# Coil_Driver_Rev_A-3V_PCH-1.net
KiCad netlist of a schematic drawn in Altium Designer
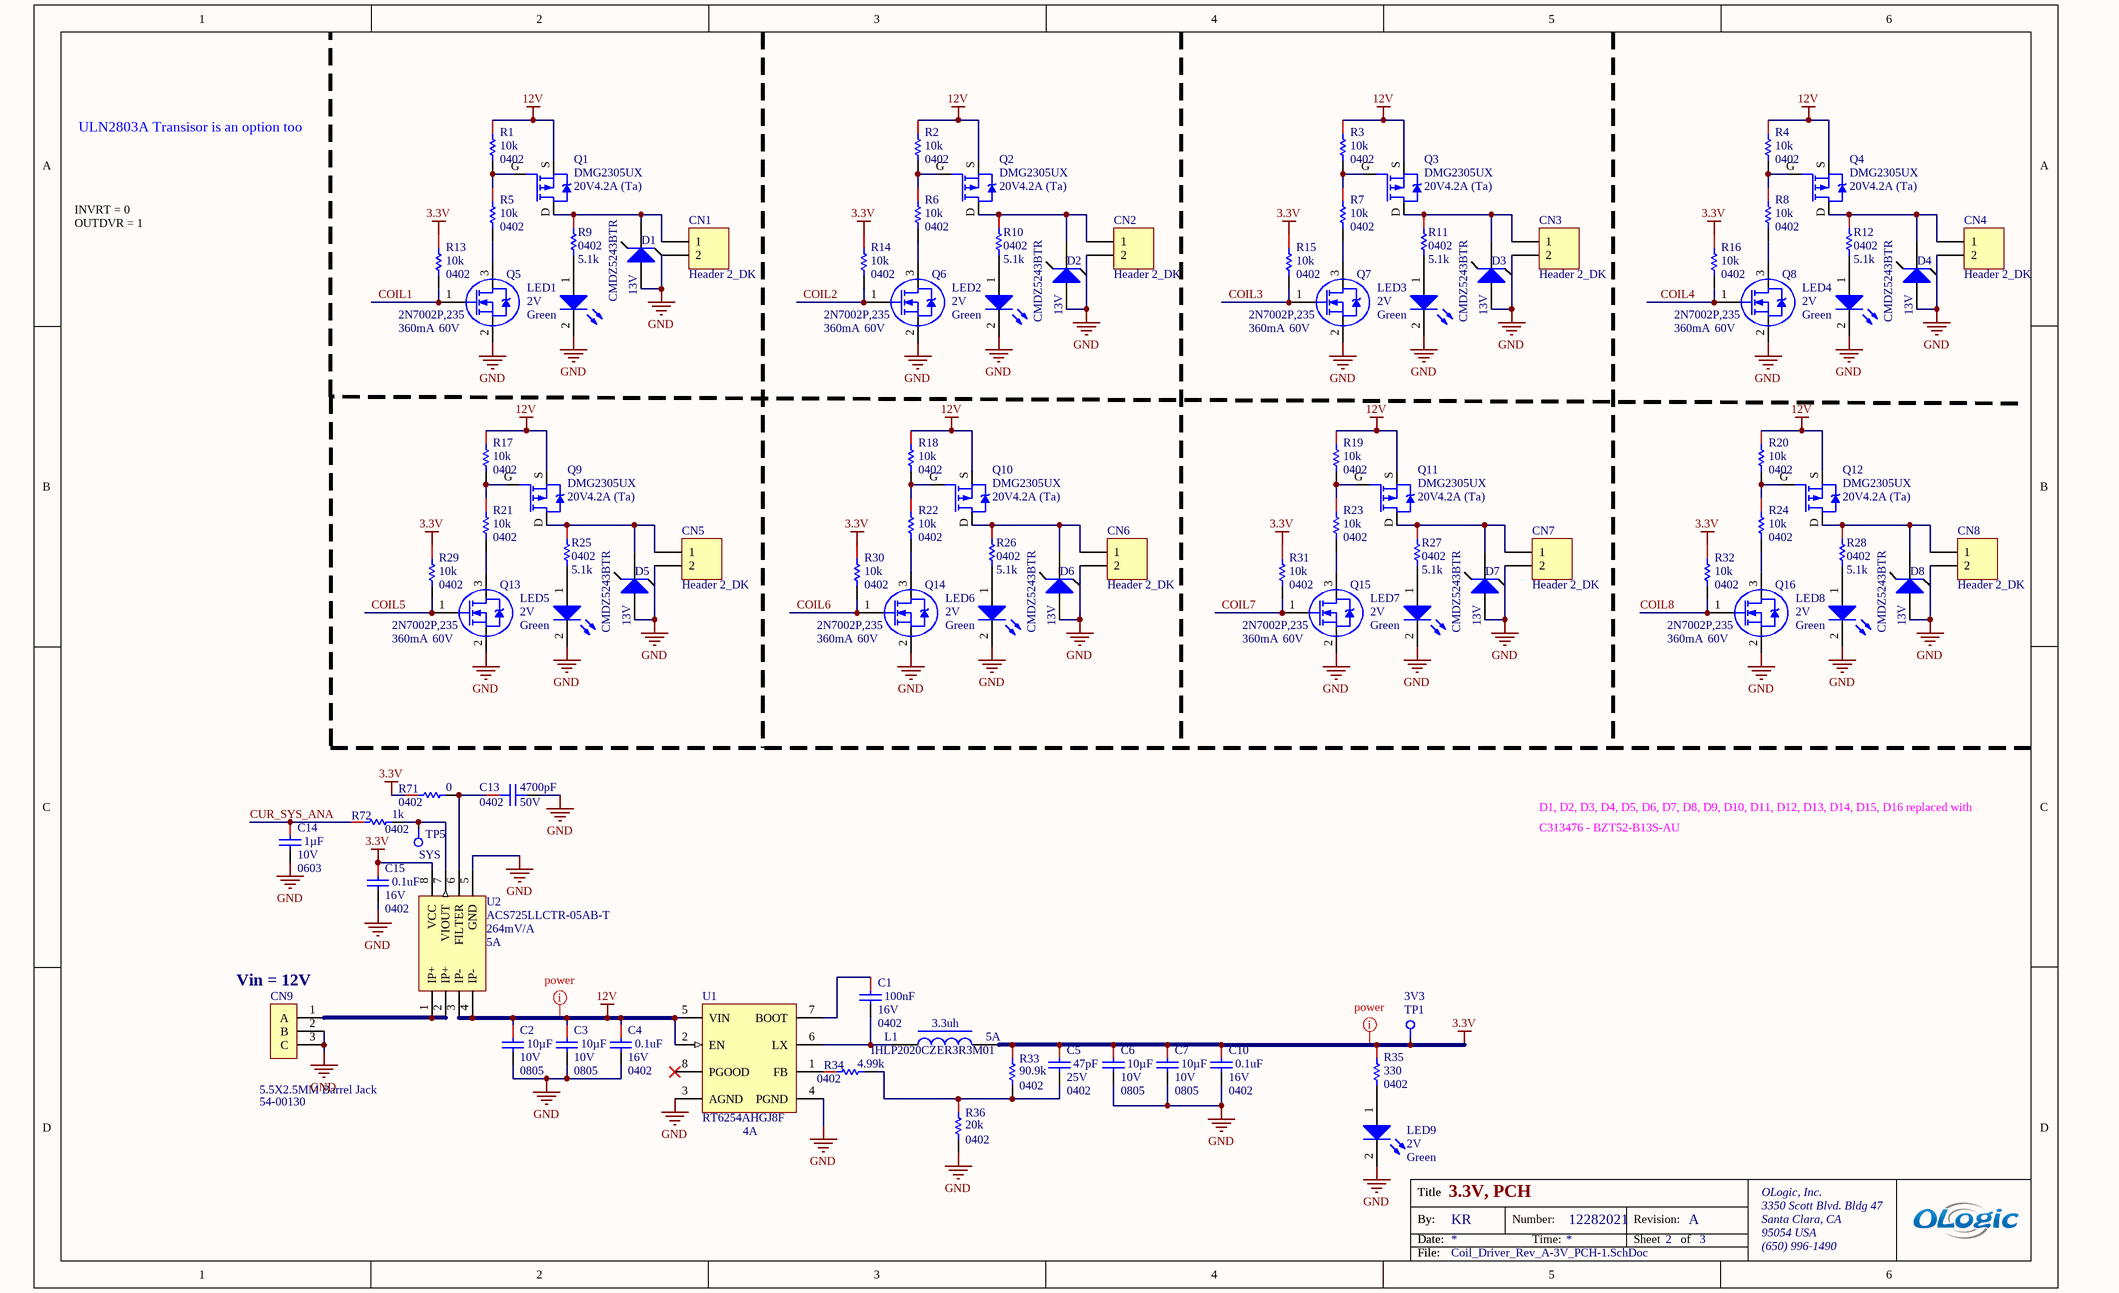
[diagram p0: Coil_Driver_Rev_A-3V_PCH-1.SchDoc]

(export (version "E")
  (design (tool "Eeschema 10.0.6"))
  (components
    (comp (ref "C1")
      (value "CAP CER 0.1UF 16V X5R 0402")
      (footprint "CAPC0402(1005)_L")
      (description "±10% 16V Ceramic Capacitor X5R 0402 (1005 Metric)")
      (fields
        (field (name "VOLTAGE (RATED)") "16V")
        (field (name "PACKAGE (IMPERIAL)") "0402")
        (field (name "TOLERANCE") "10%")
        (field (name "CAPACITANCE") "100nF")
        (field (name "MANUFACTURER") "Taiyo Yuden")
      )
      (libsource (lib "OLogic Nexus Vault") (part "OL_Capacitor"))
    )
    (comp (ref "C2")
      (value "CAP CER 10UF 10V X7R 0805")
      (footprint "CAPC0805(2012)_L")
      (description "10µF ±10% 10V Ceramic Capacitor X7R 0805 (2012 Metric)")
      (fields
        (field (name "VOLTAGE (RATED)") "10V")
        (field (name "PACKAGE (IMPERIAL)") "0805")
        (field (name "CAPACITANCE") "10µF")
        (field (name "TOLERANCE") "10%")
        (field (name "MANUFACTURER PART NUMBER") "GRM21BR71A106KA73K")
      )
      (libsource (lib "OLogic Nexus Vault") (part "OL_Capacitor"))
    )
    (comp (ref "C3")
      (value "CAP CER 10UF 10V X7R 0805")
      (footprint "CAPC0805(2012)_L")
      (description "10µF ±10% 10V Ceramic Capacitor X7R 0805 (2012 Metric)")
      (fields
        (field (name "VOLTAGE (RATED)") "10V")
        (field (name "PACKAGE (IMPERIAL)") "0805")
        (field (name "CAPACITANCE") "10µF")
        (field (name "TOLERANCE") "10%")
        (field (name "MANUFACTURER PART NUMBER") "GRM21BR71A106KA73K")
      )
      (libsource (lib "OLogic Nexus Vault") (part "OL_Capacitor"))
    )
    (comp (ref "C4")
      (value "CAP CER 0.1UF 16V X5R 0402")
      (footprint "CAPC0402(1005)_L")
      (description "±10% 16V Ceramic Capacitor X5R 0402 (1005 Metric)")
      (fields
        (field (name "PACKAGE (IMPERIAL)") "0402")
        (field (name "VOLTAGE (RATED)") "16V")
        (field (name "CAPACITANCE") "0.1uF")
        (field (name "MANUFACTURER") "Taiyo Yuden")
        (field (name "MANUFACTURER PART NUMBER") "EMK105BJ104KV-F")
      )
      (libsource (lib "OLogic Nexus Vault") (part "OL_Capacitor"))
    )
    (comp (ref "C5")
      (value "CAP CER 47PF 25V C0G/NP0 0402")
      (footprint "CAPC0402(1005)_L")
      (description "47pF ±5% 25V Ceramic Capacitor C0G, NP0 0402 (1005 Metric)")
      (fields
        (field (name "PACKAGE (IMPERIAL)") "0402")
        (field (name "VOLTAGE (RATED)") "25V")
        (field (name "CAPACITANCE") "47pF")
        (field (name "MANUFACTURER PART NUMBER") "C0402C470J3GACTU")
        (field (name "TOLERANCE") "5%")
      )
      (libsource (lib "OLogic Nexus Vault") (part "OL_Capacitor"))
    )
    (comp (ref "C6")
      (value "CAP CER 10UF 10V X7R 0805")
      (footprint "CAPC0805(2012)_L")
      (description "10µF ±10% 10V Ceramic Capacitor X7R 0805 (2012 Metric)")
      (fields
        (field (name "VOLTAGE (RATED)") "10V")
        (field (name "PACKAGE (IMPERIAL)") "0805")
        (field (name "CAPACITANCE") "10µF")
        (field (name "TOLERANCE") "10%")
        (field (name "MANUFACTURER PART NUMBER") "GRM21BR71A106KA73K")
      )
      (libsource (lib "OLogic Nexus Vault") (part "OL_Capacitor"))
    )
    (comp (ref "C7")
      (value "CAP CER 10UF 10V X7R 0805")
      (footprint "CAPC0805(2012)_L")
      (description "10µF ±10% 10V Ceramic Capacitor X7R 0805 (2012 Metric)")
      (fields
        (field (name "VOLTAGE (RATED)") "10V")
        (field (name "PACKAGE (IMPERIAL)") "0805")
        (field (name "CAPACITANCE") "10µF")
        (field (name "TOLERANCE") "10%")
        (field (name "MANUFACTURER PART NUMBER") "GRM21BR71A106KA73K")
      )
      (libsource (lib "OLogic Nexus Vault") (part "OL_Capacitor"))
    )
    (comp (ref "C10")
      (value "CAP CER 0.1UF 16V X5R 0402")
      (footprint "CAPC0402(1005)_L")
      (description "±10% 16V Ceramic Capacitor X5R 0402 (1005 Metric)")
      (fields
        (field (name "PACKAGE (IMPERIAL)") "0402")
        (field (name "VOLTAGE (RATED)") "16V")
        (field (name "CAPACITANCE") "0.1uF")
        (field (name "MANUFACTURER") "Taiyo Yuden")
        (field (name "MANUFACTURER PART NUMBER") "EMK105BJ104KV-F")
      )
      (libsource (lib "OLogic Nexus Vault") (part "OL_Capacitor"))
    )
    (comp (ref "C13")
      (value "4700pF")
      (footprint "CAPC0402(1005)_N")
      (description "CAP CER 4700PF 50V X7R 0402")
      (fields
        (field (name "TOLERANCE") "10%")
        (field (name "VOLTAGE (RATED)") "50V")
        (field (name "PACKAGE (IMPERIAL)") "0402")
      )
      (libsource (lib "OLogic Nexus Vault") (part "=Capacitance"))
    )
    (comp (ref "C14")
      (value "1uF")
      (footprint "CAPC0603(1608)_L")
      (description "PREFERRED (<3.3V): CAP CER 1UF 10V X7R 0603")
      (fields
        (field (name "CAPACITANCE") "1µF")
        (field (name "VOLTAGE (RATED)") "10V")
        (field (name "PACKAGE (IMPERIAL)") "0603")
        (field (name "TOLERANCE") "10%")
      )
      (libsource (lib "OLogic Nexus Vault") (part "Bob's Test Generic Capacitor (Non-Polarized)"))
    )
    (comp (ref "C15")
      (value "0.1uF")
      (footprint "CAPC0402(1005)_L")
      (description "CAP CER 0.1UF 16v X7R 0402")
      (fields
        (field (name "VOLTAGE (RATED)") "16V")
        (field (name "PACKAGE (IMPERIAL)") "0402")
        (field (name "TOLERANCE") "10%")
      )
      (libsource (lib "") (part "=Capacitance_1"))
    )
    (comp (ref "CN1")
      (value "Header 2_DK")
      (footprint "HDR1X2")
      (description "Header, 2-Pin")
      (fields
        (field (name "MANUFACTURER PART NUMBER") "826936-2")
        (field (name "MANUFACTURER") "TE Connectivity AMP Connectors")
      )
      (libsource (lib "OLogic Nexus Vault") (part "Header 2_DK"))
    )
    (comp (ref "CN2")
      (value "Header 2_DK")
      (footprint "HDR1X2")
      (description "Header, 2-Pin")
      (fields
        (field (name "MANUFACTURER PART NUMBER") "826936-2")
        (field (name "MANUFACTURER") "TE Connectivity AMP Connectors")
      )
      (libsource (lib "OLogic Nexus Vault") (part "Header 2_DK"))
    )
    (comp (ref "CN3")
      (value "Header 2_DK")
      (footprint "HDR1X2")
      (description "Header, 2-Pin")
      (fields
        (field (name "MANUFACTURER PART NUMBER") "826936-2")
        (field (name "MANUFACTURER") "TE Connectivity AMP Connectors")
      )
      (libsource (lib "OLogic Nexus Vault") (part "Header 2_DK"))
    )
    (comp (ref "CN4")
      (value "Header 2_DK")
      (footprint "HDR1X2")
      (description "Header, 2-Pin")
      (fields
        (field (name "MANUFACTURER PART NUMBER") "826936-2")
        (field (name "MANUFACTURER") "TE Connectivity AMP Connectors")
      )
      (libsource (lib "OLogic Nexus Vault") (part "Header 2_DK"))
    )
    (comp (ref "CN5")
      (value "Header 2_DK")
      (footprint "HDR1X2")
      (description "Header, 2-Pin")
      (fields
        (field (name "MANUFACTURER PART NUMBER") "826936-2")
        (field (name "MANUFACTURER") "TE Connectivity AMP Connectors")
      )
      (libsource (lib "OLogic Nexus Vault") (part "Header 2_DK"))
    )
    (comp (ref "CN6")
      (value "Header 2_DK")
      (footprint "HDR1X2")
      (description "Header, 2-Pin")
      (fields
        (field (name "MANUFACTURER PART NUMBER") "826936-2")
        (field (name "MANUFACTURER") "TE Connectivity AMP Connectors")
      )
      (libsource (lib "OLogic Nexus Vault") (part "Header 2_DK"))
    )
    (comp (ref "CN7")
      (value "Header 2_DK")
      (footprint "HDR1X2")
      (description "Header, 2-Pin")
      (fields
        (field (name "MANUFACTURER PART NUMBER") "826936-2")
        (field (name "MANUFACTURER") "TE Connectivity AMP Connectors")
      )
      (libsource (lib "OLogic Nexus Vault") (part "Header 2_DK"))
    )
    (comp (ref "CN8")
      (value "Header 2_DK")
      (footprint "HDR1X2")
      (description "Header, 2-Pin")
      (fields
        (field (name "MANUFACTURER PART NUMBER") "826936-2")
        (field (name "MANUFACTURER") "TE Connectivity AMP Connectors")
      )
      (libsource (lib "OLogic Nexus Vault") (part "Header 2_DK"))
    )
    (comp (ref "CN9")
      (value "5.5X2.5MM Barrel Jack")
      (footprint "54-00130")
      (description "CONN JACK R/A PCB 5.5X2.5MM")
      (fields
        (field (name "MANUFACTURER PART NUMBER") "54-00130")
        (field (name "MANUFACTURER") "Tensility International Corp")
      )
      (libsource (lib "OLogic Nexus Vault") (part "54-00130"))
    )
    (comp (ref "D1")
      (value "CMDZ5243BTR")
      (footprint "SOD-323")
      (description "DIODE ZENER 13V 250MW SOD323")
      (fields (field (name "TOLERANCE") "5%") (field (name "ZENER VOLTAGE") "13V"))
      (libsource (lib "OLogic Nexus Vault") (part "13V 250mW"))
    )
    (comp (ref "D2")
      (value "CMDZ5243BTR")
      (footprint "SOD-323")
      (description "DIODE ZENER 13V 250MW SOD323")
      (fields (field (name "TOLERANCE") "5%") (field (name "ZENER VOLTAGE") "13V"))
      (libsource (lib "OLogic Nexus Vault") (part "13V 250mW"))
    )
    (comp (ref "D3")
      (value "CMDZ5243BTR")
      (footprint "SOD-323")
      (description "DIODE ZENER 13V 250MW SOD323")
      (fields (field (name "TOLERANCE") "5%") (field (name "ZENER VOLTAGE") "13V"))
      (libsource (lib "OLogic Nexus Vault") (part "13V 250mW"))
    )
    (comp (ref "D4")
      (value "CMDZ5243BTR")
      (footprint "SOD-323")
      (description "DIODE ZENER 13V 250MW SOD323")
      (fields (field (name "TOLERANCE") "5%") (field (name "ZENER VOLTAGE") "13V"))
      (libsource (lib "OLogic Nexus Vault") (part "13V 250mW"))
    )
    (comp (ref "D5")
      (value "CMDZ5243BTR")
      (footprint "SOD-323")
      (description "DIODE ZENER 13V 250MW SOD323")
      (fields (field (name "TOLERANCE") "5%") (field (name "ZENER VOLTAGE") "13V"))
      (libsource (lib "OLogic Nexus Vault") (part "13V 250mW"))
    )
    (comp (ref "D6")
      (value "CMDZ5243BTR")
      (footprint "SOD-323")
      (description "DIODE ZENER 13V 250MW SOD323")
      (fields (field (name "TOLERANCE") "5%") (field (name "ZENER VOLTAGE") "13V"))
      (libsource (lib "OLogic Nexus Vault") (part "13V 250mW"))
    )
    (comp (ref "D7")
      (value "CMDZ5243BTR")
      (footprint "SOD-323")
      (description "DIODE ZENER 13V 250MW SOD323")
      (fields (field (name "TOLERANCE") "5%") (field (name "ZENER VOLTAGE") "13V"))
      (libsource (lib "OLogic Nexus Vault") (part "13V 250mW"))
    )
    (comp (ref "D8")
      (value "CMDZ5243BTR")
      (footprint "SOD-323")
      (description "DIODE ZENER 13V 250MW SOD323")
      (fields (field (name "TOLERANCE") "5%") (field (name "ZENER VOLTAGE") "13V"))
      (libsource (lib "OLogic Nexus Vault") (part "13V 250mW"))
    )
    (comp (ref "L1")
      (value "IHLP2020CZER3R3M01")
      (footprint "INDP5252X30N")
      (description "FIXED IND 3.3UH 5A 54.7 MOHM SMD")
      (fields
        (field (name "TOLERANCE") "20%")
        (field (name "INDUCTANCE") "3.3uh")
        (field (name "CURRENT RATING") "5A")
      )
      (libsource (lib "OLogic Nexus Vault") (part "INDUCTOR SHIELDED 150UH .53A SMD"))
    )
    (comp (ref "LED1")
      (value "LTST-C191KGKT")
      (footprint "SM-LED-0603")
      (description "LED GREEN CLEAR THIN 0603 SMD")
      (fields
        (field (name "MANUFACTURER") "Lite-On Inc")
        (field (name "VOLTAGE - FORWARD (VF) (TYP)") "2V")
        (field (name "COLOR") "Green")
      )
      (libsource (lib "OLogic Nexus Vault") (part "OL_LED"))
    )
    (comp (ref "LED2")
      (value "LTST-C191KGKT")
      (footprint "SM-LED-0603")
      (description "LED GREEN CLEAR THIN 0603 SMD")
      (fields
        (field (name "MANUFACTURER") "Lite-On Inc")
        (field (name "VOLTAGE - FORWARD (VF) (TYP)") "2V")
        (field (name "COLOR") "Green")
      )
      (libsource (lib "OLogic Nexus Vault") (part "OL_LED"))
    )
    (comp (ref "LED3")
      (value "LTST-C191KGKT")
      (footprint "SM-LED-0603")
      (description "LED GREEN CLEAR THIN 0603 SMD")
      (fields
        (field (name "MANUFACTURER") "Lite-On Inc")
        (field (name "VOLTAGE - FORWARD (VF) (TYP)") "2V")
        (field (name "COLOR") "Green")
      )
      (libsource (lib "OLogic Nexus Vault") (part "OL_LED"))
    )
    (comp (ref "LED4")
      (value "LTST-C191KGKT")
      (footprint "SM-LED-0603")
      (description "LED GREEN CLEAR THIN 0603 SMD")
      (fields
        (field (name "MANUFACTURER") "Lite-On Inc")
        (field (name "VOLTAGE - FORWARD (VF) (TYP)") "2V")
        (field (name "COLOR") "Green")
      )
      (libsource (lib "OLogic Nexus Vault") (part "OL_LED"))
    )
    (comp (ref "LED5")
      (value "LTST-C191KGKT")
      (footprint "SM-LED-0603")
      (description "LED GREEN CLEAR THIN 0603 SMD")
      (fields
        (field (name "MANUFACTURER") "Lite-On Inc")
        (field (name "VOLTAGE - FORWARD (VF) (TYP)") "2V")
        (field (name "COLOR") "Green")
      )
      (libsource (lib "OLogic Nexus Vault") (part "OL_LED"))
    )
    (comp (ref "LED6")
      (value "LTST-C191KGKT")
      (footprint "SM-LED-0603")
      (description "LED GREEN CLEAR THIN 0603 SMD")
      (fields
        (field (name "MANUFACTURER") "Lite-On Inc")
        (field (name "VOLTAGE - FORWARD (VF) (TYP)") "2V")
        (field (name "COLOR") "Green")
      )
      (libsource (lib "OLogic Nexus Vault") (part "OL_LED"))
    )
    (comp (ref "LED7")
      (value "LTST-C191KGKT")
      (footprint "SM-LED-0603")
      (description "LED GREEN CLEAR THIN 0603 SMD")
      (fields
        (field (name "MANUFACTURER") "Lite-On Inc")
        (field (name "VOLTAGE - FORWARD (VF) (TYP)") "2V")
        (field (name "COLOR") "Green")
      )
      (libsource (lib "OLogic Nexus Vault") (part "OL_LED"))
    )
    (comp (ref "LED8")
      (value "LTST-C191KGKT")
      (footprint "SM-LED-0603")
      (description "LED GREEN CLEAR THIN 0603 SMD")
      (fields
        (field (name "MANUFACTURER") "Lite-On Inc")
        (field (name "VOLTAGE - FORWARD (VF) (TYP)") "2V")
        (field (name "COLOR") "Green")
      )
      (libsource (lib "OLogic Nexus Vault") (part "OL_LED"))
    )
    (comp (ref "LED9")
      (value "LTST-C191KGKT")
      (footprint "SM-LED-0603")
      (description "LED GREEN CLEAR THIN 0603 SMD")
      (fields
        (field (name "MANUFACTURER") "Lite-On Inc")
        (field (name "VOLTAGE - FORWARD (VF) (TYP)") "2V")
        (field (name "COLOR") "Green")
      )
      (libsource (lib "OLogic Nexus Vault") (part "OL_LED"))
    )
    (comp (ref "Q1")
      (value "DMG2305UX")
      (footprint "DMG2305UX-7")
      (description "MOSFET P-CH 20V 4.2A SOT23")
      (fields
        (field (name "MANUFACTURER PART NUMBER") "DMG2305UX-7")
        (field (name "MANUFACTURER") "Diodes Incorporated")
        (field (name "CURRENT - CONTINUOUS DRAIN (ID) @ 25°C") "4.2A (Ta)")
        (field (name "DRAIN TO SOURCE VOLTAGE (VDSS)") "20V")
        (field (name "CREATOR") "osman")
      )
      (libsource (lib "OLogic Nexus Vault") (part "DMG2305UX"))
    )
    (comp (ref "Q2")
      (value "DMG2305UX")
      (footprint "DMG2305UX-7")
      (description "MOSFET P-CH 20V 4.2A SOT23")
      (fields
        (field (name "MANUFACTURER PART NUMBER") "DMG2305UX-7")
        (field (name "MANUFACTURER") "Diodes Incorporated")
        (field (name "CURRENT - CONTINUOUS DRAIN (ID) @ 25°C") "4.2A (Ta)")
        (field (name "DRAIN TO SOURCE VOLTAGE (VDSS)") "20V")
        (field (name "CREATOR") "osman")
      )
      (libsource (lib "OLogic Nexus Vault") (part "DMG2305UX"))
    )
    (comp (ref "Q3")
      (value "DMG2305UX")
      (footprint "DMG2305UX-7")
      (description "MOSFET P-CH 20V 4.2A SOT23")
      (fields
        (field (name "MANUFACTURER PART NUMBER") "DMG2305UX-7")
        (field (name "MANUFACTURER") "Diodes Incorporated")
        (field (name "CURRENT - CONTINUOUS DRAIN (ID) @ 25°C") "4.2A (Ta)")
        (field (name "DRAIN TO SOURCE VOLTAGE (VDSS)") "20V")
        (field (name "CREATOR") "osman")
      )
      (libsource (lib "OLogic Nexus Vault") (part "DMG2305UX"))
    )
    (comp (ref "Q4")
      (value "DMG2305UX")
      (footprint "DMG2305UX-7")
      (description "MOSFET P-CH 20V 4.2A SOT23")
      (fields
        (field (name "MANUFACTURER PART NUMBER") "DMG2305UX-7")
        (field (name "MANUFACTURER") "Diodes Incorporated")
        (field (name "CURRENT - CONTINUOUS DRAIN (ID) @ 25°C") "4.2A (Ta)")
        (field (name "DRAIN TO SOURCE VOLTAGE (VDSS)") "20V")
        (field (name "CREATOR") "osman")
      )
      (libsource (lib "OLogic Nexus Vault") (part "DMG2305UX"))
    )
    (comp (ref "Q5")
      (value "2N7002P,235")
      (footprint "SOT23-3L")
      (description "MOSFET N-CH 60V 0.36A SOT-23")
      (fields
        (field (name "CONTINUOUS DRAIN CURRENT (ID)") "360mA")
        (field (name "MANUFACTURER") "NXP Semiconductors")
        (field (name "DRAIN TO SOURCE VOLTAGE (VDSS)") "60V")
      )
      (libsource (lib "OLogic Nexus Vault") (part "2N7002P,235"))
    )
    (comp (ref "Q6")
      (value "2N7002P,235")
      (footprint "SOT23-3L")
      (description "MOSFET N-CH 60V 0.36A SOT-23")
      (fields
        (field (name "CONTINUOUS DRAIN CURRENT (ID)") "360mA")
        (field (name "MANUFACTURER") "NXP Semiconductors")
        (field (name "DRAIN TO SOURCE VOLTAGE (VDSS)") "60V")
      )
      (libsource (lib "OLogic Nexus Vault") (part "2N7002P,235"))
    )
    (comp (ref "Q7")
      (value "2N7002P,235")
      (footprint "SOT23-3L")
      (description "MOSFET N-CH 60V 0.36A SOT-23")
      (fields
        (field (name "CONTINUOUS DRAIN CURRENT (ID)") "360mA")
        (field (name "MANUFACTURER") "NXP Semiconductors")
        (field (name "DRAIN TO SOURCE VOLTAGE (VDSS)") "60V")
      )
      (libsource (lib "OLogic Nexus Vault") (part "2N7002P,235"))
    )
    (comp (ref "Q8")
      (value "2N7002P,235")
      (footprint "SOT23-3L")
      (description "MOSFET N-CH 60V 0.36A SOT-23")
      (fields
        (field (name "CONTINUOUS DRAIN CURRENT (ID)") "360mA")
        (field (name "MANUFACTURER") "NXP Semiconductors")
        (field (name "DRAIN TO SOURCE VOLTAGE (VDSS)") "60V")
      )
      (libsource (lib "OLogic Nexus Vault") (part "2N7002P,235"))
    )
    (comp (ref "Q9")
      (value "DMG2305UX")
      (footprint "DMG2305UX-7")
      (description "MOSFET P-CH 20V 4.2A SOT23")
      (fields
        (field (name "MANUFACTURER PART NUMBER") "DMG2305UX-7")
        (field (name "MANUFACTURER") "Diodes Incorporated")
        (field (name "CURRENT - CONTINUOUS DRAIN (ID) @ 25°C") "4.2A (Ta)")
        (field (name "DRAIN TO SOURCE VOLTAGE (VDSS)") "20V")
        (field (name "CREATOR") "osman")
      )
      (libsource (lib "OLogic Nexus Vault") (part "DMG2305UX"))
    )
    (comp (ref "Q10")
      (value "DMG2305UX")
      (footprint "DMG2305UX-7")
      (description "MOSFET P-CH 20V 4.2A SOT23")
      (fields
        (field (name "MANUFACTURER PART NUMBER") "DMG2305UX-7")
        (field (name "MANUFACTURER") "Diodes Incorporated")
        (field (name "CURRENT - CONTINUOUS DRAIN (ID) @ 25°C") "4.2A (Ta)")
        (field (name "DRAIN TO SOURCE VOLTAGE (VDSS)") "20V")
        (field (name "CREATOR") "osman")
      )
      (libsource (lib "OLogic Nexus Vault") (part "DMG2305UX"))
    )
    (comp (ref "Q11")
      (value "DMG2305UX")
      (footprint "DMG2305UX-7")
      (description "MOSFET P-CH 20V 4.2A SOT23")
      (fields
        (field (name "MANUFACTURER PART NUMBER") "DMG2305UX-7")
        (field (name "MANUFACTURER") "Diodes Incorporated")
        (field (name "CURRENT - CONTINUOUS DRAIN (ID) @ 25°C") "4.2A (Ta)")
        (field (name "DRAIN TO SOURCE VOLTAGE (VDSS)") "20V")
        (field (name "CREATOR") "osman")
      )
      (libsource (lib "OLogic Nexus Vault") (part "DMG2305UX"))
    )
    (comp (ref "Q12")
      (value "DMG2305UX")
      (footprint "DMG2305UX-7")
      (description "MOSFET P-CH 20V 4.2A SOT23")
      (fields
        (field (name "MANUFACTURER PART NUMBER") "DMG2305UX-7")
        (field (name "MANUFACTURER") "Diodes Incorporated")
        (field (name "CURRENT - CONTINUOUS DRAIN (ID) @ 25°C") "4.2A (Ta)")
        (field (name "DRAIN TO SOURCE VOLTAGE (VDSS)") "20V")
        (field (name "CREATOR") "osman")
      )
      (libsource (lib "OLogic Nexus Vault") (part "DMG2305UX"))
    )
    (comp (ref "Q13")
      (value "2N7002P,235")
      (footprint "SOT23-3L")
      (description "MOSFET N-CH 60V 0.36A SOT-23")
      (fields
        (field (name "CONTINUOUS DRAIN CURRENT (ID)") "360mA")
        (field (name "MANUFACTURER") "NXP Semiconductors")
        (field (name "DRAIN TO SOURCE VOLTAGE (VDSS)") "60V")
      )
      (libsource (lib "OLogic Nexus Vault") (part "2N7002P,235"))
    )
    (comp (ref "Q14")
      (value "2N7002P,235")
      (footprint "SOT23-3L")
      (description "MOSFET N-CH 60V 0.36A SOT-23")
      (fields
        (field (name "CONTINUOUS DRAIN CURRENT (ID)") "360mA")
        (field (name "MANUFACTURER") "NXP Semiconductors")
        (field (name "DRAIN TO SOURCE VOLTAGE (VDSS)") "60V")
      )
      (libsource (lib "OLogic Nexus Vault") (part "2N7002P,235"))
    )
    (comp (ref "Q15")
      (value "2N7002P,235")
      (footprint "SOT23-3L")
      (description "MOSFET N-CH 60V 0.36A SOT-23")
      (fields
        (field (name "CONTINUOUS DRAIN CURRENT (ID)") "360mA")
        (field (name "MANUFACTURER") "NXP Semiconductors")
        (field (name "DRAIN TO SOURCE VOLTAGE (VDSS)") "60V")
      )
      (libsource (lib "OLogic Nexus Vault") (part "2N7002P,235"))
    )
    (comp (ref "Q16")
      (value "2N7002P,235")
      (footprint "SOT23-3L")
      (description "MOSFET N-CH 60V 0.36A SOT-23")
      (fields
        (field (name "CONTINUOUS DRAIN CURRENT (ID)") "360mA")
        (field (name "MANUFACTURER") "NXP Semiconductors")
        (field (name "DRAIN TO SOURCE VOLTAGE (VDSS)") "60V")
      )
      (libsource (lib "OLogic Nexus Vault") (part "2N7002P,235"))
    )
    (comp (ref "R1")
      (value "RES 10K OHM 0.1% 1/16W 0402")
      (footprint "RESC0402(1005)_L")
      (description "10 kOhms ±0.1% 0.063W, 1/16W Chip Resistor 0402 (1005 Metric) Automotive AEC-Q200 Thin Film")
      (fields
        (field (name "TOLERANCE") "0.1%")
        (field (name "RESISTANCE") "10k")
        (field (name "CASE CODE (IMPERIAL)") "0402")
      )
      (libsource (lib "OLogic Nexus Vault") (part "OL_Resistor"))
    )
    (comp (ref "R2")
      (value "RES 10K OHM 0.1% 1/16W 0402")
      (footprint "RESC0402(1005)_L")
      (description "10 kOhms ±0.1% 0.063W, 1/16W Chip Resistor 0402 (1005 Metric) Automotive AEC-Q200 Thin Film")
      (fields
        (field (name "TOLERANCE") "0.1%")
        (field (name "RESISTANCE") "10k")
        (field (name "CASE CODE (IMPERIAL)") "0402")
      )
      (libsource (lib "OLogic Nexus Vault") (part "OL_Resistor"))
    )
    (comp (ref "R3")
      (value "RES 10K OHM 0.1% 1/16W 0402")
      (footprint "RESC0402(1005)_L")
      (description "10 kOhms ±0.1% 0.063W, 1/16W Chip Resistor 0402 (1005 Metric) Automotive AEC-Q200 Thin Film")
      (fields
        (field (name "TOLERANCE") "0.1%")
        (field (name "RESISTANCE") "10k")
        (field (name "CASE CODE (IMPERIAL)") "0402")
      )
      (libsource (lib "OLogic Nexus Vault") (part "OL_Resistor"))
    )
    (comp (ref "R4")
      (value "RES 10K OHM 0.1% 1/16W 0402")
      (footprint "RESC0402(1005)_L")
      (description "10 kOhms ±0.1% 0.063W, 1/16W Chip Resistor 0402 (1005 Metric) Automotive AEC-Q200 Thin Film")
      (fields
        (field (name "TOLERANCE") "0.1%")
        (field (name "RESISTANCE") "10k")
        (field (name "CASE CODE (IMPERIAL)") "0402")
      )
      (libsource (lib "OLogic Nexus Vault") (part "OL_Resistor"))
    )
    (comp (ref "R5")
      (value "RES 10K OHM 0.1% 1/16W 0402")
      (footprint "RESC0402(1005)_L")
      (description "10 kOhms ±0.1% 0.063W, 1/16W Chip Resistor 0402 (1005 Metric) Automotive AEC-Q200 Thin Film")
      (fields
        (field (name "TOLERANCE") "0.1%")
        (field (name "RESISTANCE") "10k")
        (field (name "CASE CODE (IMPERIAL)") "0402")
      )
      (libsource (lib "OLogic Nexus Vault") (part "OL_Resistor"))
    )
    (comp (ref "R6")
      (value "RES 10K OHM 0.1% 1/16W 0402")
      (footprint "RESC0402(1005)_L")
      (description "10 kOhms ±0.1% 0.063W, 1/16W Chip Resistor 0402 (1005 Metric) Automotive AEC-Q200 Thin Film")
      (fields
        (field (name "TOLERANCE") "0.1%")
        (field (name "RESISTANCE") "10k")
        (field (name "CASE CODE (IMPERIAL)") "0402")
      )
      (libsource (lib "OLogic Nexus Vault") (part "OL_Resistor"))
    )
    (comp (ref "R7")
      (value "RES 10K OHM 0.1% 1/16W 0402")
      (footprint "RESC0402(1005)_L")
      (description "10 kOhms ±0.1% 0.063W, 1/16W Chip Resistor 0402 (1005 Metric) Automotive AEC-Q200 Thin Film")
      (fields
        (field (name "TOLERANCE") "0.1%")
        (field (name "RESISTANCE") "10k")
        (field (name "CASE CODE (IMPERIAL)") "0402")
      )
      (libsource (lib "OLogic Nexus Vault") (part "OL_Resistor"))
    )
    (comp (ref "R8")
      (value "RES 10K OHM 0.1% 1/16W 0402")
      (footprint "RESC0402(1005)_L")
      (description "10 kOhms ±0.1% 0.063W, 1/16W Chip Resistor 0402 (1005 Metric) Automotive AEC-Q200 Thin Film")
      (fields
        (field (name "TOLERANCE") "0.1%")
        (field (name "RESISTANCE") "10k")
        (field (name "CASE CODE (IMPERIAL)") "0402")
      )
      (libsource (lib "OLogic Nexus Vault") (part "OL_Resistor"))
    )
    (comp (ref "R9")
      (value "5.1K")
      (footprint "RESC0402(1005)_L")
      (description "RES SMD 5.1K OHM 1% 1/10W 0402")
      (fields
        (field (name "PACKAGE (IMPERIAL)") "0402")
        (field (name "RESISTANCE") "5.1k")
        (field (name "POWER") "63mW")
        (field (name "TOLERANCE") "1%")
      )
      (libsource (lib "OLogic Nexus Vault") (part "=Resistance"))
    )
    (comp (ref "R10")
      (value "5.1K")
      (footprint "RESC0402(1005)_L")
      (description "RES SMD 5.1K OHM 1% 1/10W 0402")
      (fields
        (field (name "PACKAGE (IMPERIAL)") "0402")
        (field (name "RESISTANCE") "5.1k")
        (field (name "POWER") "63mW")
        (field (name "TOLERANCE") "1%")
      )
      (libsource (lib "OLogic Nexus Vault") (part "=Resistance"))
    )
    (comp (ref "R11")
      (value "5.1K")
      (footprint "RESC0402(1005)_L")
      (description "RES SMD 5.1K OHM 1% 1/10W 0402")
      (fields
        (field (name "PACKAGE (IMPERIAL)") "0402")
        (field (name "RESISTANCE") "5.1k")
        (field (name "POWER") "63mW")
        (field (name "TOLERANCE") "1%")
      )
      (libsource (lib "OLogic Nexus Vault") (part "=Resistance"))
    )
    (comp (ref "R12")
      (value "5.1K")
      (footprint "RESC0402(1005)_L")
      (description "RES SMD 5.1K OHM 1% 1/10W 0402")
      (fields
        (field (name "PACKAGE (IMPERIAL)") "0402")
        (field (name "RESISTANCE") "5.1k")
        (field (name "POWER") "63mW")
        (field (name "TOLERANCE") "1%")
      )
      (libsource (lib "OLogic Nexus Vault") (part "=Resistance"))
    )
    (comp (ref "R13")
      (value "RES 10K OHM 0.1% 1/16W 0402")
      (footprint "RESC0402(1005)_L")
      (description "10 kOhms ±0.1% 0.063W, 1/16W Chip Resistor 0402 (1005 Metric) Automotive AEC-Q200 Thin Film")
      (fields
        (field (name "TOLERANCE") "0.1%")
        (field (name "RESISTANCE") "10k")
        (field (name "CASE CODE (IMPERIAL)") "0402")
      )
      (libsource (lib "OLogic Nexus Vault") (part "OL_Resistor"))
    )
    (comp (ref "R14")
      (value "RES 10K OHM 0.1% 1/16W 0402")
      (footprint "RESC0402(1005)_L")
      (description "10 kOhms ±0.1% 0.063W, 1/16W Chip Resistor 0402 (1005 Metric) Automotive AEC-Q200 Thin Film")
      (fields
        (field (name "TOLERANCE") "0.1%")
        (field (name "RESISTANCE") "10k")
        (field (name "CASE CODE (IMPERIAL)") "0402")
      )
      (libsource (lib "OLogic Nexus Vault") (part "OL_Resistor"))
    )
    (comp (ref "R15")
      (value "RES 10K OHM 0.1% 1/16W 0402")
      (footprint "RESC0402(1005)_L")
      (description "10 kOhms ±0.1% 0.063W, 1/16W Chip Resistor 0402 (1005 Metric) Automotive AEC-Q200 Thin Film")
      (fields
        (field (name "TOLERANCE") "0.1%")
        (field (name "RESISTANCE") "10k")
        (field (name "CASE CODE (IMPERIAL)") "0402")
      )
      (libsource (lib "OLogic Nexus Vault") (part "OL_Resistor"))
    )
    (comp (ref "R16")
      (value "RES 10K OHM 0.1% 1/16W 0402")
      (footprint "RESC0402(1005)_L")
      (description "10 kOhms ±0.1% 0.063W, 1/16W Chip Resistor 0402 (1005 Metric) Automotive AEC-Q200 Thin Film")
      (fields
        (field (name "TOLERANCE") "0.1%")
        (field (name "RESISTANCE") "10k")
        (field (name "CASE CODE (IMPERIAL)") "0402")
      )
      (libsource (lib "OLogic Nexus Vault") (part "OL_Resistor"))
    )
    (comp (ref "R17")
      (value "RES 10K OHM 0.1% 1/16W 0402")
      (footprint "RESC0402(1005)_L")
      (description "10 kOhms ±0.1% 0.063W, 1/16W Chip Resistor 0402 (1005 Metric) Automotive AEC-Q200 Thin Film")
      (fields
        (field (name "TOLERANCE") "0.1%")
        (field (name "RESISTANCE") "10k")
        (field (name "CASE CODE (IMPERIAL)") "0402")
      )
      (libsource (lib "OLogic Nexus Vault") (part "OL_Resistor"))
    )
    (comp (ref "R18")
      (value "RES 10K OHM 0.1% 1/16W 0402")
      (footprint "RESC0402(1005)_L")
      (description "10 kOhms ±0.1% 0.063W, 1/16W Chip Resistor 0402 (1005 Metric) Automotive AEC-Q200 Thin Film")
      (fields
        (field (name "TOLERANCE") "0.1%")
        (field (name "RESISTANCE") "10k")
        (field (name "CASE CODE (IMPERIAL)") "0402")
      )
      (libsource (lib "OLogic Nexus Vault") (part "OL_Resistor"))
    )
    (comp (ref "R19")
      (value "RES 10K OHM 0.1% 1/16W 0402")
      (footprint "RESC0402(1005)_L")
      (description "10 kOhms ±0.1% 0.063W, 1/16W Chip Resistor 0402 (1005 Metric) Automotive AEC-Q200 Thin Film")
      (fields
        (field (name "TOLERANCE") "0.1%")
        (field (name "RESISTANCE") "10k")
        (field (name "CASE CODE (IMPERIAL)") "0402")
      )
      (libsource (lib "OLogic Nexus Vault") (part "OL_Resistor"))
    )
    (comp (ref "R20")
      (value "RES 10K OHM 0.1% 1/16W 0402")
      (footprint "RESC0402(1005)_L")
      (description "10 kOhms ±0.1% 0.063W, 1/16W Chip Resistor 0402 (1005 Metric) Automotive AEC-Q200 Thin Film")
      (fields
        (field (name "TOLERANCE") "0.1%")
        (field (name "RESISTANCE") "10k")
        (field (name "CASE CODE (IMPERIAL)") "0402")
      )
      (libsource (lib "OLogic Nexus Vault") (part "OL_Resistor"))
    )
    (comp (ref "R21")
      (value "RES 10K OHM 0.1% 1/16W 0402")
      (footprint "RESC0402(1005)_L")
      (description "10 kOhms ±0.1% 0.063W, 1/16W Chip Resistor 0402 (1005 Metric) Automotive AEC-Q200 Thin Film")
      (fields
        (field (name "TOLERANCE") "0.1%")
        (field (name "RESISTANCE") "10k")
        (field (name "CASE CODE (IMPERIAL)") "0402")
      )
      (libsource (lib "OLogic Nexus Vault") (part "OL_Resistor"))
    )
    (comp (ref "R22")
      (value "RES 10K OHM 0.1% 1/16W 0402")
      (footprint "RESC0402(1005)_L")
      (description "10 kOhms ±0.1% 0.063W, 1/16W Chip Resistor 0402 (1005 Metric) Automotive AEC-Q200 Thin Film")
      (fields
        (field (name "TOLERANCE") "0.1%")
        (field (name "RESISTANCE") "10k")
        (field (name "CASE CODE (IMPERIAL)") "0402")
      )
      (libsource (lib "OLogic Nexus Vault") (part "OL_Resistor"))
    )
    (comp (ref "R23")
      (value "RES 10K OHM 0.1% 1/16W 0402")
      (footprint "RESC0402(1005)_L")
      (description "10 kOhms ±0.1% 0.063W, 1/16W Chip Resistor 0402 (1005 Metric) Automotive AEC-Q200 Thin Film")
      (fields
        (field (name "TOLERANCE") "0.1%")
        (field (name "RESISTANCE") "10k")
        (field (name "CASE CODE (IMPERIAL)") "0402")
      )
      (libsource (lib "OLogic Nexus Vault") (part "OL_Resistor"))
    )
    (comp (ref "R24")
      (value "RES 10K OHM 0.1% 1/16W 0402")
      (footprint "RESC0402(1005)_L")
      (description "10 kOhms ±0.1% 0.063W, 1/16W Chip Resistor 0402 (1005 Metric) Automotive AEC-Q200 Thin Film")
      (fields
        (field (name "TOLERANCE") "0.1%")
        (field (name "RESISTANCE") "10k")
        (field (name "CASE CODE (IMPERIAL)") "0402")
      )
      (libsource (lib "OLogic Nexus Vault") (part "OL_Resistor"))
    )
    (comp (ref "R25")
      (value "5.1K")
      (footprint "RESC0402(1005)_L")
      (description "RES SMD 5.1K OHM 1% 1/10W 0402")
      (fields
        (field (name "PACKAGE (IMPERIAL)") "0402")
        (field (name "RESISTANCE") "5.1k")
        (field (name "POWER") "63mW")
        (field (name "TOLERANCE") "1%")
      )
      (libsource (lib "OLogic Nexus Vault") (part "=Resistance"))
    )
    (comp (ref "R26")
      (value "5.1K")
      (footprint "RESC0402(1005)_L")
      (description "RES SMD 5.1K OHM 1% 1/10W 0402")
      (fields
        (field (name "PACKAGE (IMPERIAL)") "0402")
        (field (name "RESISTANCE") "5.1k")
        (field (name "POWER") "63mW")
        (field (name "TOLERANCE") "1%")
      )
      (libsource (lib "OLogic Nexus Vault") (part "=Resistance"))
    )
    (comp (ref "R27")
      (value "5.1K")
      (footprint "RESC0402(1005)_L")
      (description "RES SMD 5.1K OHM 1% 1/10W 0402")
      (fields
        (field (name "PACKAGE (IMPERIAL)") "0402")
        (field (name "RESISTANCE") "5.1k")
        (field (name "POWER") "63mW")
        (field (name "TOLERANCE") "1%")
      )
      (libsource (lib "OLogic Nexus Vault") (part "=Resistance"))
    )
    (comp (ref "R28")
      (value "5.1K")
      (footprint "RESC0402(1005)_L")
      (description "RES SMD 5.1K OHM 1% 1/10W 0402")
      (fields
        (field (name "PACKAGE (IMPERIAL)") "0402")
        (field (name "RESISTANCE") "5.1k")
        (field (name "POWER") "63mW")
        (field (name "TOLERANCE") "1%")
      )
      (libsource (lib "OLogic Nexus Vault") (part "=Resistance"))
    )
    (comp (ref "R29")
      (value "RES 10K OHM 0.1% 1/16W 0402")
      (footprint "RESC0402(1005)_L")
      (description "10 kOhms ±0.1% 0.063W, 1/16W Chip Resistor 0402 (1005 Metric) Automotive AEC-Q200 Thin Film")
      (fields
        (field (name "TOLERANCE") "0.1%")
        (field (name "RESISTANCE") "10k")
        (field (name "CASE CODE (IMPERIAL)") "0402")
      )
      (libsource (lib "OLogic Nexus Vault") (part "OL_Resistor"))
    )
    (comp (ref "R30")
      (value "RES 10K OHM 0.1% 1/16W 0402")
      (footprint "RESC0402(1005)_L")
      (description "10 kOhms ±0.1% 0.063W, 1/16W Chip Resistor 0402 (1005 Metric) Automotive AEC-Q200 Thin Film")
      (fields
        (field (name "TOLERANCE") "0.1%")
        (field (name "RESISTANCE") "10k")
        (field (name "CASE CODE (IMPERIAL)") "0402")
      )
      (libsource (lib "OLogic Nexus Vault") (part "OL_Resistor"))
    )
    (comp (ref "R31")
      (value "RES 10K OHM 0.1% 1/16W 0402")
      (footprint "RESC0402(1005)_L")
      (description "10 kOhms ±0.1% 0.063W, 1/16W Chip Resistor 0402 (1005 Metric) Automotive AEC-Q200 Thin Film")
      (fields
        (field (name "TOLERANCE") "0.1%")
        (field (name "RESISTANCE") "10k")
        (field (name "CASE CODE (IMPERIAL)") "0402")
      )
      (libsource (lib "OLogic Nexus Vault") (part "OL_Resistor"))
    )
    (comp (ref "R32")
      (value "RES 10K OHM 0.1% 1/16W 0402")
      (footprint "RESC0402(1005)_L")
      (description "10 kOhms ±0.1% 0.063W, 1/16W Chip Resistor 0402 (1005 Metric) Automotive AEC-Q200 Thin Film")
      (fields
        (field (name "TOLERANCE") "0.1%")
        (field (name "RESISTANCE") "10k")
        (field (name "CASE CODE (IMPERIAL)") "0402")
      )
      (libsource (lib "OLogic Nexus Vault") (part "OL_Resistor"))
    )
    (comp (ref "R33")
      (value "RES 90.9K OHM 1% 1/16W 0402")
      (footprint "RESC0402(1005)_L")
      (description "90.9 kOhms ±1% 0.063W, 1/16W Chip Resistor 0402 (1005 Metric) Automotive AEC-Q200 Thick Film")
      (fields
        (field (name "PACKAGE (IMPERIAL)") "0402")
        (field (name "TOLERANCE") "1%")
        (field (name "POWER") "63mW")
        (field (name "RESISTANCE") "90.9k")
      )
      (libsource (lib "OLogic Nexus Vault") (part "=Resistance"))
    )
    (comp (ref "R34")
      (value "4.99K")
      (footprint "RESC0402(1005)_L")
      (description "RES SMD 4.99K OHM 1% 1/16W 0402")
      (fields
        (field (name "PACKAGE (IMPERIAL)") "0402")
        (field (name "TOLERANCE") "1%")
        (field (name "RESISTANCE") "4.99k")
        (field (name "POWER") "63mW")
      )
      (libsource (lib "OLogic Nexus Vault") (part "=Resistance"))
    )
    (comp (ref "R35")
      (value "330")
      (footprint "RESC0402(1005)_L")
      (description "RES SMD 330 OHM 1% 1/10W 0402")
      (fields
        (field (name "PACKAGE (IMPERIAL)") "0402")
        (field (name "RESISTANCE") "330")
        (field (name "POWER") "63mW")
        (field (name "TOLERANCE") "1%")
      )
      (libsource (lib "OLogic Nexus Vault") (part "=Resistance"))
    )
    (comp (ref "R36")
      (value "20K")
      (footprint "RESC0402(1005)_L")
      (description "RES 20K OHM 1% 1/10W 0402")
      (fields
        (field (name "PACKAGE (IMPERIAL)") "0402")
        (field (name "RESISTANCE") "20k")
        (field (name "POWER") "63mW")
        (field (name "TOLERANCE") "1%")
      )
      (libsource (lib "OLogic Nexus Vault") (part "=Resistance"))
    )
    (comp (ref "R71")
      (value "~")
      (footprint "RESC0402(1005)_N")
      (description "RES 0.0 OHM JUMPER 0402 1/10W SMD")
      (fields
        (field (name "PACKAGE (IMPERIAL)") "0402")
        (field (name "RESISTANCE") "0")
        (field (name "POWER") "63mW")
        (field (name "TOLERANCE") "0%")
      )
      (libsource (lib "OLogic Nexus Vault") (part "=Resistance"))
    )
    (comp (ref "R72")
      (value "1K")
      (footprint "RESC0402(1005)_N")
      (description "RES 1K OHM 1% 1/16W 0402")
      (fields
        (field (name "PACKAGE (IMPERIAL)") "0402")
        (field (name "POWER") "63mW")
        (field (name "TOLERANCE") "1%")
        (field (name "RESISTANCE") "1k")
      )
      (libsource (lib "OLogic Nexus Vault") (part "=Resistance"))
    )
    (comp (ref "TP1")
      (value "3V3")
      (footprint "Pogo-Testpoint")
      (description "Test Point- Current one")
      (libsource (lib "OLogic Nexus Vault") (part "TestPoint"))
    )
    (comp (ref "TP5")
      (value "SYS")
      (footprint "Pogo-Testpoint")
      (description "Test Point- Current one")
      (libsource (lib "OLogic Nexus Vault") (part "TestPoint"))
    )
    (comp (ref "U1")
      (value "RT6254AHGJ8F")
      (footprint "TSOT-23-8")
      (description "IC REG BUCK ADJ 4A TSOT23-8")
      (fields (field (name "OUTPUT CURRENT") "4A"))
      (libsource (lib "OLogic Nexus Vault") (part "RT6254AHGJ8F"))
    )
    (comp (ref "U2")
      (value "ACS725LLCTR-05AB-T")
      (footprint "SOG.050/8A")
      (description "Current Sensor 5A 1 Channel Hall Effect, Differential Bidirectional")
      (fields (field (name "SENSITIVITY") "264mV/A") (field (name "CURRENT - SENSING") "5A"))
      (libsource (lib "OLogic Nexus Vault") (part "ACS725LLCTR-05AB-T"))
    )
  )
  (nets
    (net (code "1") (name "/COIL1") (class "Default")
      (node (ref "Q5") (pin "1") (pinfunction "G_1") (pintype "passive"))
      (node (ref "R13") (pin "2") (pinfunction "2_2") (pintype "passive"))
    )
    (net (code "2") (name "/COIL2") (class "Default")
      (node (ref "Q6") (pin "1") (pinfunction "G_1") (pintype "passive"))
      (node (ref "R14") (pin "2") (pinfunction "2_2") (pintype "passive"))
    )
    (net (code "3") (name "/COIL3") (class "Default")
      (node (ref "Q7") (pin "1") (pinfunction "G_1") (pintype "passive"))
      (node (ref "R15") (pin "2") (pinfunction "2_2") (pintype "passive"))
    )
    (net (code "4") (name "/COIL4") (class "Default")
      (node (ref "Q8") (pin "1") (pinfunction "G_1") (pintype "passive"))
      (node (ref "R16") (pin "2") (pinfunction "2_2") (pintype "passive"))
    )
    (net (code "5") (name "/COIL5") (class "Default")
      (node (ref "Q13") (pin "1") (pinfunction "G_1") (pintype "passive"))
      (node (ref "R29") (pin "2") (pinfunction "2_2") (pintype "passive"))
    )
    (net (code "6") (name "/COIL6") (class "Default")
      (node (ref "Q14") (pin "1") (pinfunction "G_1") (pintype "passive"))
      (node (ref "R30") (pin "2") (pinfunction "2_2") (pintype "passive"))
    )
    (net (code "7") (name "/COIL7") (class "Default")
      (node (ref "Q15") (pin "1") (pinfunction "G_1") (pintype "passive"))
      (node (ref "R31") (pin "2") (pinfunction "2_2") (pintype "passive"))
    )
    (net (code "8") (name "/COIL8") (class "Default")
      (node (ref "Q16") (pin "1") (pinfunction "G_1") (pintype "passive"))
      (node (ref "R32") (pin "2") (pinfunction "2_2") (pintype "passive"))
    )
    (net (code "9") (name "/CUR_SYS_ANA") (class "Default")
      (node (ref "C14") (pin "1") (pinfunction "1_1") (pintype "passive"))
      (node (ref "R72") (pin "1") (pinfunction "1_1") (pintype "passive"))
    )
    (net (code "10") (name "3.3V") (class "Default")
      (node (ref "C10") (pin "1") (pinfunction "1_1") (pintype "passive"))
      (node (ref "C15") (pin "1") (pinfunction "1_1") (pintype "passive"))
      (node (ref "C5") (pin "1") (pinfunction "1_1") (pintype "passive"))
      (node (ref "C6") (pin "1") (pinfunction "1_1") (pintype "passive"))
      (node (ref "C7") (pin "1") (pinfunction "1_1") (pintype "passive"))
      (node (ref "L1") (pin "2") (pinfunction "2_2") (pintype "passive"))
      (node (ref "R13") (pin "1") (pinfunction "1_1") (pintype "passive"))
      (node (ref "R14") (pin "1") (pinfunction "1_1") (pintype "passive"))
      (node (ref "R15") (pin "1") (pinfunction "1_1") (pintype "passive"))
      (node (ref "R16") (pin "1") (pinfunction "1_1") (pintype "passive"))
      (node (ref "R29") (pin "1") (pinfunction "1_1") (pintype "passive"))
      (node (ref "R30") (pin "1") (pinfunction "1_1") (pintype "passive"))
      (node (ref "R31") (pin "1") (pinfunction "1_1") (pintype "passive"))
      (node (ref "R32") (pin "1") (pinfunction "1_1") (pintype "passive"))
      (node (ref "R33") (pin "1") (pinfunction "1_1") (pintype "passive"))
      (node (ref "R35") (pin "1") (pinfunction "1_1") (pintype "passive"))
      (node (ref "R71") (pin "1") (pinfunction "1_1") (pintype "passive"))
      (node (ref "TP1") (pin "1") (pinfunction "1_1") (pintype "passive"))
      (node (ref "U2") (pin "8") (pinfunction "VCC_8") (pintype "passive"))
    )
    (net (code "11") (name "12V") (class "Default")
      (node (ref "C2") (pin "1") (pinfunction "1_1") (pintype "passive"))
      (node (ref "C3") (pin "1") (pinfunction "1_1") (pintype "passive"))
      (node (ref "C4") (pin "1") (pinfunction "1_1") (pintype "passive"))
      (node (ref "Q1") (pin "S") (pinfunction "S_S") (pintype "passive"))
      (node (ref "Q10") (pin "S") (pinfunction "S_S") (pintype "passive"))
      (node (ref "Q11") (pin "S") (pinfunction "S_S") (pintype "passive"))
      (node (ref "Q12") (pin "S") (pinfunction "S_S") (pintype "passive"))
      (node (ref "Q2") (pin "S") (pinfunction "S_S") (pintype "passive"))
      (node (ref "Q3") (pin "S") (pinfunction "S_S") (pintype "passive"))
      (node (ref "Q4") (pin "S") (pinfunction "S_S") (pintype "passive"))
      (node (ref "Q9") (pin "S") (pinfunction "S_S") (pintype "passive"))
      (node (ref "R1") (pin "1") (pinfunction "1_1") (pintype "passive"))
      (node (ref "R17") (pin "1") (pinfunction "1_1") (pintype "passive"))
      (node (ref "R18") (pin "1") (pinfunction "1_1") (pintype "passive"))
      (node (ref "R19") (pin "1") (pinfunction "1_1") (pintype "passive"))
      (node (ref "R2") (pin "1") (pinfunction "1_1") (pintype "passive"))
      (node (ref "R20") (pin "1") (pinfunction "1_1") (pintype "passive"))
      (node (ref "R3") (pin "1") (pinfunction "1_1") (pintype "passive"))
      (node (ref "R4") (pin "1") (pinfunction "1_1") (pintype "passive"))
      (node (ref "U1") (pin "2") (pinfunction "EN_2") (pintype "input"))
      (node (ref "U1") (pin "5") (pinfunction "VIN_5") (pintype "power_in"))
      (node (ref "U2") (pin "3") (pinfunction "IP-_3") (pintype "passive"))
      (node (ref "U2") (pin "4") (pinfunction "IP-_4") (pintype "passive"))
    )
    (net (code "12") (name "GND") (class "Default")
      (node (ref "C10") (pin "2") (pinfunction "2_2") (pintype "passive"))
      (node (ref "C13") (pin "2") (pinfunction "2_2") (pintype "passive"))
      (node (ref "C14") (pin "2") (pinfunction "2_2") (pintype "passive"))
      (node (ref "C15") (pin "2") (pinfunction "2_2") (pintype "passive"))
      (node (ref "C2") (pin "2") (pinfunction "2_2") (pintype "passive"))
      (node (ref "C3") (pin "2") (pinfunction "2_2") (pintype "passive"))
      (node (ref "C4") (pin "2") (pinfunction "2_2") (pintype "passive"))
      (node (ref "C6") (pin "2") (pinfunction "2_2") (pintype "passive"))
      (node (ref "C7") (pin "2") (pinfunction "2_2") (pintype "passive"))
      (node (ref "CN1") (pin "2") (pinfunction "2_2") (pintype "passive"))
      (node (ref "CN2") (pin "2") (pinfunction "2_2") (pintype "passive"))
      (node (ref "CN3") (pin "2") (pinfunction "2_2") (pintype "passive"))
      (node (ref "CN4") (pin "2") (pinfunction "2_2") (pintype "passive"))
      (node (ref "CN5") (pin "2") (pinfunction "2_2") (pintype "passive"))
      (node (ref "CN6") (pin "2") (pinfunction "2_2") (pintype "passive"))
      (node (ref "CN7") (pin "2") (pinfunction "2_2") (pintype "passive"))
      (node (ref "CN8") (pin "2") (pinfunction "2_2") (pintype "passive"))
      (node (ref "CN9") (pin "2") (pinfunction "B_2") (pintype "passive"))
      (node (ref "CN9") (pin "3") (pinfunction "C_3") (pintype "passive"))
      (node (ref "D1") (pin "2") (pinfunction "A_2") (pintype "passive"))
      (node (ref "D2") (pin "2") (pinfunction "A_2") (pintype "passive"))
      (node (ref "D3") (pin "2") (pinfunction "A_2") (pintype "passive"))
      (node (ref "D4") (pin "2") (pinfunction "A_2") (pintype "passive"))
      (node (ref "D5") (pin "2") (pinfunction "A_2") (pintype "passive"))
      (node (ref "D6") (pin "2") (pinfunction "A_2") (pintype "passive"))
      (node (ref "D7") (pin "2") (pinfunction "A_2") (pintype "passive"))
      (node (ref "D8") (pin "2") (pinfunction "A_2") (pintype "passive"))
      (node (ref "LED1") (pin "2") (pinfunction "K_2") (pintype "passive"))
      (node (ref "LED2") (pin "2") (pinfunction "K_2") (pintype "passive"))
      (node (ref "LED3") (pin "2") (pinfunction "K_2") (pintype "passive"))
      (node (ref "LED4") (pin "2") (pinfunction "K_2") (pintype "passive"))
      (node (ref "LED5") (pin "2") (pinfunction "K_2") (pintype "passive"))
      (node (ref "LED6") (pin "2") (pinfunction "K_2") (pintype "passive"))
      (node (ref "LED7") (pin "2") (pinfunction "K_2") (pintype "passive"))
      (node (ref "LED8") (pin "2") (pinfunction "K_2") (pintype "passive"))
      (node (ref "LED9") (pin "2") (pinfunction "K_2") (pintype "passive"))
      (node (ref "Q13") (pin "2") (pinfunction "S_2") (pintype "passive"))
      (node (ref "Q14") (pin "2") (pinfunction "S_2") (pintype "passive"))
      (node (ref "Q15") (pin "2") (pinfunction "S_2") (pintype "passive"))
      (node (ref "Q16") (pin "2") (pinfunction "S_2") (pintype "passive"))
      (node (ref "Q5") (pin "2") (pinfunction "S_2") (pintype "passive"))
      (node (ref "Q6") (pin "2") (pinfunction "S_2") (pintype "passive"))
      (node (ref "Q7") (pin "2") (pinfunction "S_2") (pintype "passive"))
      (node (ref "Q8") (pin "2") (pinfunction "S_2") (pintype "passive"))
      (node (ref "R36") (pin "2") (pinfunction "2_2") (pintype "passive"))
      (node (ref "U1") (pin "3") (pinfunction "AGND_3") (pintype "power_in"))
      (node (ref "U1") (pin "4") (pinfunction "PGND_4") (pintype "power_in"))
      (node (ref "U2") (pin "5") (pinfunction "GND_5") (pintype "passive"))
    )
    (net (code "13") (name "Net-(C5-Pad2)") (class "Default")
      (node (ref "C5") (pin "2") (pinfunction "2_2") (pintype "passive"))
      (node (ref "R33") (pin "2") (pinfunction "2_2") (pintype "passive"))
      (node (ref "R34") (pin "2") (pinfunction "2_2") (pintype "passive"))
      (node (ref "R36") (pin "1") (pinfunction "1_1") (pintype "passive"))
    )
    (net (code "14") (name "Net-(CN9-A)") (class "Default")
      (node (ref "CN9") (pin "1") (pinfunction "A_1") (pintype "passive"))
      (node (ref "U2") (pin "1") (pinfunction "IP+_1") (pintype "passive"))
      (node (ref "U2") (pin "2") (pinfunction "IP+_2") (pintype "passive"))
    )
    (net (code "15") (name "Net-(D1-K)") (class "Default")
      (node (ref "CN1") (pin "1") (pinfunction "1_1") (pintype "passive"))
      (node (ref "D1") (pin "1") (pinfunction "K_1") (pintype "passive"))
      (node (ref "Q1") (pin "D") (pinfunction "D_D") (pintype "passive"))
      (node (ref "R9") (pin "1") (pinfunction "1_1") (pintype "passive"))
    )
    (net (code "16") (name "Net-(D2-K)") (class "Default")
      (node (ref "CN2") (pin "1") (pinfunction "1_1") (pintype "passive"))
      (node (ref "D2") (pin "1") (pinfunction "K_1") (pintype "passive"))
      (node (ref "Q2") (pin "D") (pinfunction "D_D") (pintype "passive"))
      (node (ref "R10") (pin "1") (pinfunction "1_1") (pintype "passive"))
    )
    (net (code "17") (name "Net-(D3-K)") (class "Default")
      (node (ref "CN3") (pin "1") (pinfunction "1_1") (pintype "passive"))
      (node (ref "D3") (pin "1") (pinfunction "K_1") (pintype "passive"))
      (node (ref "Q3") (pin "D") (pinfunction "D_D") (pintype "passive"))
      (node (ref "R11") (pin "1") (pinfunction "1_1") (pintype "passive"))
    )
    (net (code "18") (name "Net-(D4-K)") (class "Default")
      (node (ref "CN4") (pin "1") (pinfunction "1_1") (pintype "passive"))
      (node (ref "D4") (pin "1") (pinfunction "K_1") (pintype "passive"))
      (node (ref "Q4") (pin "D") (pinfunction "D_D") (pintype "passive"))
      (node (ref "R12") (pin "1") (pinfunction "1_1") (pintype "passive"))
    )
    (net (code "19") (name "Net-(D5-K)") (class "Default")
      (node (ref "CN5") (pin "1") (pinfunction "1_1") (pintype "passive"))
      (node (ref "D5") (pin "1") (pinfunction "K_1") (pintype "passive"))
      (node (ref "Q9") (pin "D") (pinfunction "D_D") (pintype "passive"))
      (node (ref "R25") (pin "1") (pinfunction "1_1") (pintype "passive"))
    )
    (net (code "20") (name "Net-(D6-K)") (class "Default")
      (node (ref "CN6") (pin "1") (pinfunction "1_1") (pintype "passive"))
      (node (ref "D6") (pin "1") (pinfunction "K_1") (pintype "passive"))
      (node (ref "Q10") (pin "D") (pinfunction "D_D") (pintype "passive"))
      (node (ref "R26") (pin "1") (pinfunction "1_1") (pintype "passive"))
    )
    (net (code "21") (name "Net-(D7-K)") (class "Default")
      (node (ref "CN7") (pin "1") (pinfunction "1_1") (pintype "passive"))
      (node (ref "D7") (pin "1") (pinfunction "K_1") (pintype "passive"))
      (node (ref "Q11") (pin "D") (pinfunction "D_D") (pintype "passive"))
      (node (ref "R27") (pin "1") (pinfunction "1_1") (pintype "passive"))
    )
    (net (code "22") (name "Net-(D8-K)") (class "Default")
      (node (ref "CN8") (pin "1") (pinfunction "1_1") (pintype "passive"))
      (node (ref "D8") (pin "1") (pinfunction "K_1") (pintype "passive"))
      (node (ref "Q12") (pin "D") (pinfunction "D_D") (pintype "passive"))
      (node (ref "R28") (pin "1") (pinfunction "1_1") (pintype "passive"))
    )
    (net (code "23") (name "Net-(LED1-A)") (class "Default")
      (node (ref "LED1") (pin "1") (pinfunction "A_1") (pintype "passive"))
      (node (ref "R9") (pin "2") (pinfunction "2_2") (pintype "passive"))
    )
    (net (code "24") (name "Net-(LED2-A)") (class "Default")
      (node (ref "LED2") (pin "1") (pinfunction "A_1") (pintype "passive"))
      (node (ref "R10") (pin "2") (pinfunction "2_2") (pintype "passive"))
    )
    (net (code "25") (name "Net-(LED3-A)") (class "Default")
      (node (ref "LED3") (pin "1") (pinfunction "A_1") (pintype "passive"))
      (node (ref "R11") (pin "2") (pinfunction "2_2") (pintype "passive"))
    )
    (net (code "26") (name "Net-(LED4-A)") (class "Default")
      (node (ref "LED4") (pin "1") (pinfunction "A_1") (pintype "passive"))
      (node (ref "R12") (pin "2") (pinfunction "2_2") (pintype "passive"))
    )
    (net (code "27") (name "Net-(LED5-A)") (class "Default")
      (node (ref "LED5") (pin "1") (pinfunction "A_1") (pintype "passive"))
      (node (ref "R25") (pin "2") (pinfunction "2_2") (pintype "passive"))
    )
    (net (code "28") (name "Net-(LED6-A)") (class "Default")
      (node (ref "LED6") (pin "1") (pinfunction "A_1") (pintype "passive"))
      (node (ref "R26") (pin "2") (pinfunction "2_2") (pintype "passive"))
    )
    (net (code "29") (name "Net-(LED7-A)") (class "Default")
      (node (ref "LED7") (pin "1") (pinfunction "A_1") (pintype "passive"))
      (node (ref "R27") (pin "2") (pinfunction "2_2") (pintype "passive"))
    )
    (net (code "30") (name "Net-(LED8-A)") (class "Default")
      (node (ref "LED8") (pin "1") (pinfunction "A_1") (pintype "passive"))
      (node (ref "R28") (pin "2") (pinfunction "2_2") (pintype "passive"))
    )
    (net (code "31") (name "Net-(LED9-A)") (class "Default")
      (node (ref "LED9") (pin "1") (pinfunction "A_1") (pintype "passive"))
      (node (ref "R35") (pin "2") (pinfunction "2_2") (pintype "passive"))
    )
    (net (code "32") (name "Net-(Q1-PadG)") (class "Default")
      (node (ref "Q1") (pin "G") (pinfunction "G_G") (pintype "passive"))
      (node (ref "R1") (pin "2") (pinfunction "2_2") (pintype "passive"))
      (node (ref "R5") (pin "1") (pinfunction "1_1") (pintype "passive"))
    )
    (net (code "33") (name "Net-(Q2-PadG)") (class "Default")
      (node (ref "Q2") (pin "G") (pinfunction "G_G") (pintype "passive"))
      (node (ref "R2") (pin "2") (pinfunction "2_2") (pintype "passive"))
      (node (ref "R6") (pin "1") (pinfunction "1_1") (pintype "passive"))
    )
    (net (code "34") (name "Net-(Q3-PadG)") (class "Default")
      (node (ref "Q3") (pin "G") (pinfunction "G_G") (pintype "passive"))
      (node (ref "R3") (pin "2") (pinfunction "2_2") (pintype "passive"))
      (node (ref "R7") (pin "1") (pinfunction "1_1") (pintype "passive"))
    )
    (net (code "35") (name "Net-(Q4-PadG)") (class "Default")
      (node (ref "Q4") (pin "G") (pinfunction "G_G") (pintype "passive"))
      (node (ref "R4") (pin "2") (pinfunction "2_2") (pintype "passive"))
      (node (ref "R8") (pin "1") (pinfunction "1_1") (pintype "passive"))
    )
    (net (code "36") (name "Net-(Q5-D)") (class "Default")
      (node (ref "Q5") (pin "3") (pinfunction "D_3") (pintype "passive"))
      (node (ref "R5") (pin "2") (pinfunction "2_2") (pintype "passive"))
    )
    (net (code "37") (name "Net-(Q6-D)") (class "Default")
      (node (ref "Q6") (pin "3") (pinfunction "D_3") (pintype "passive"))
      (node (ref "R6") (pin "2") (pinfunction "2_2") (pintype "passive"))
    )
    (net (code "38") (name "Net-(Q7-D)") (class "Default")
      (node (ref "Q7") (pin "3") (pinfunction "D_3") (pintype "passive"))
      (node (ref "R7") (pin "2") (pinfunction "2_2") (pintype "passive"))
    )
    (net (code "39") (name "Net-(Q8-D)") (class "Default")
      (node (ref "Q8") (pin "3") (pinfunction "D_3") (pintype "passive"))
      (node (ref "R8") (pin "2") (pinfunction "2_2") (pintype "passive"))
    )
    (net (code "40") (name "Net-(Q9-PadG)") (class "Default")
      (node (ref "Q9") (pin "G") (pinfunction "G_G") (pintype "passive"))
      (node (ref "R17") (pin "2") (pinfunction "2_2") (pintype "passive"))
      (node (ref "R21") (pin "1") (pinfunction "1_1") (pintype "passive"))
    )
    (net (code "41") (name "Net-(Q10-PadG)") (class "Default")
      (node (ref "Q10") (pin "G") (pinfunction "G_G") (pintype "passive"))
      (node (ref "R18") (pin "2") (pinfunction "2_2") (pintype "passive"))
      (node (ref "R22") (pin "1") (pinfunction "1_1") (pintype "passive"))
    )
    (net (code "42") (name "Net-(Q11-PadG)") (class "Default")
      (node (ref "Q11") (pin "G") (pinfunction "G_G") (pintype "passive"))
      (node (ref "R19") (pin "2") (pinfunction "2_2") (pintype "passive"))
      (node (ref "R23") (pin "1") (pinfunction "1_1") (pintype "passive"))
    )
    (net (code "43") (name "Net-(Q12-PadG)") (class "Default")
      (node (ref "Q12") (pin "G") (pinfunction "G_G") (pintype "passive"))
      (node (ref "R20") (pin "2") (pinfunction "2_2") (pintype "passive"))
      (node (ref "R24") (pin "1") (pinfunction "1_1") (pintype "passive"))
    )
    (net (code "44") (name "Net-(Q13-D)") (class "Default")
      (node (ref "Q13") (pin "3") (pinfunction "D_3") (pintype "passive"))
      (node (ref "R21") (pin "2") (pinfunction "2_2") (pintype "passive"))
    )
    (net (code "45") (name "Net-(Q14-D)") (class "Default")
      (node (ref "Q14") (pin "3") (pinfunction "D_3") (pintype "passive"))
      (node (ref "R22") (pin "2") (pinfunction "2_2") (pintype "passive"))
    )
    (net (code "46") (name "Net-(Q15-D)") (class "Default")
      (node (ref "Q15") (pin "3") (pinfunction "D_3") (pintype "passive"))
      (node (ref "R23") (pin "2") (pinfunction "2_2") (pintype "passive"))
    )
    (net (code "47") (name "Net-(Q16-D)") (class "Default")
      (node (ref "Q16") (pin "3") (pinfunction "D_3") (pintype "passive"))
      (node (ref "R24") (pin "2") (pinfunction "2_2") (pintype "passive"))
    )
    (net (code "48") (name "Net-(U1-BOOT)") (class "Default")
      (node (ref "C1") (pin "1") (pinfunction "1_1") (pintype "passive"))
      (node (ref "U1") (pin "7") (pinfunction "BOOT_7") (pintype "power_in"))
    )
    (net (code "49") (name "Net-(U1-FB)") (class "Default")
      (node (ref "R34") (pin "1") (pinfunction "1_1") (pintype "passive"))
      (node (ref "U1") (pin "1") (pinfunction "FB_1") (pintype "passive"))
    )
    (net (code "50") (name "Net-(U1-LX)") (class "Default")
      (node (ref "C1") (pin "2") (pinfunction "2_2") (pintype "passive"))
      (node (ref "L1") (pin "1") (pinfunction "1_1") (pintype "passive"))
      (node (ref "U1") (pin "6") (pinfunction "LX_6") (pintype "passive"))
    )
    (net (code "51") (name "Net-(U2-FILTER)") (class "Default")
      (node (ref "C13") (pin "1") (pinfunction "1_1") (pintype "passive"))
      (node (ref "R71") (pin "2") (pinfunction "2_2") (pintype "passive"))
      (node (ref "U2") (pin "6") (pinfunction "FILTER_6") (pintype "passive"))
    )
    (net (code "52") (name "Net-(U2-VIOUT)") (class "Default")
      (node (ref "R72") (pin "2") (pinfunction "2_2") (pintype "passive"))
      (node (ref "TP5") (pin "1") (pinfunction "1_1") (pintype "passive"))
      (node (ref "U2") (pin "7") (pinfunction "VIOUT_7") (pintype "output"))
    )
    (net (code "53") (name "unconnected-(U1-PGOOD-Pad8)") (class "Default")
      (node (ref "U1") (pin "8") (pinfunction "PGOOD_8") (pintype "power_in+no_connect"))
    )
  )
)
